# powersupply1.net
KiCad netlist of a schematic drawn in Altium Designer
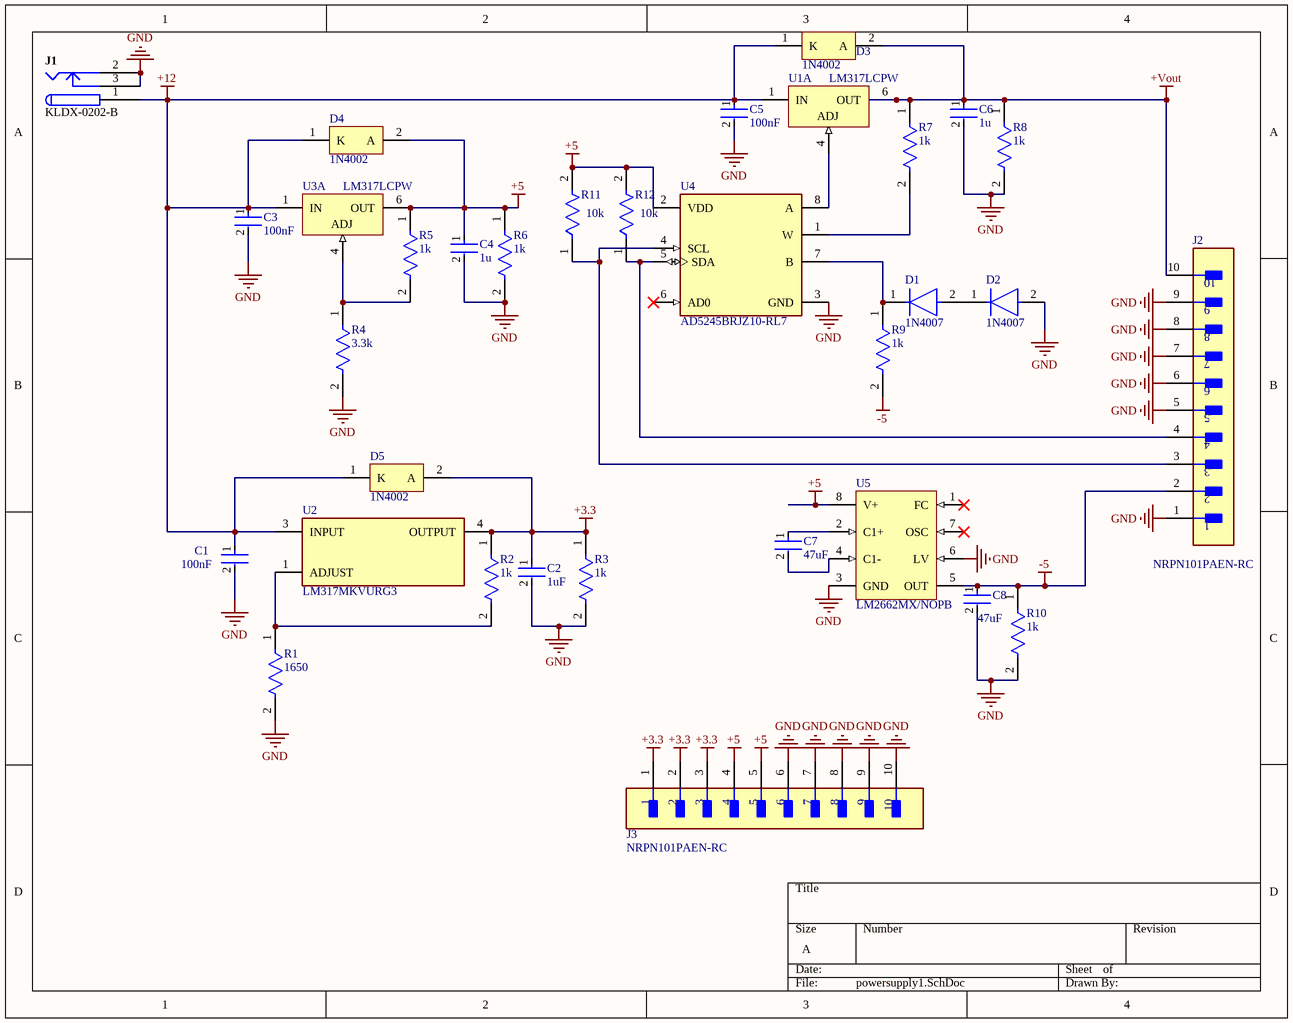
[diagram p0: powersupply1.SchDoc]

(export (version "E")
  (design (tool "Eeschema 10.0.6"))
  (components
    (comp (ref "C1")
      (value "100nF")
      (footprint "FP-CC0805-0_85-MFG")
      (description "CAP CER 0.1UF 25V X7R 0805")
      (fields (field (name "MANUFACTURER") "Yageo") (field (name "TOLERANCE") "0.2"))
      (libsource (lib "Altium Content Vault") (part "11868f565c42a9108669ba33697ecf6"))
    )
    (comp (ref "C2")
      (value "1uF")
      (footprint "FP-CC0805-0_85-MFG")
      (description "CAP CER 1UF 6.3V X5R 0805")
      (fields (field (name "MANUFACTURER") "Yageo") (field (name "TOLERANCE") "0.1"))
      (libsource (lib "Altium Content Vault") (part "11868f565c42a9108669ba33697ecf6"))
    )
    (comp (ref "C3")
      (value "100nF")
      (footprint "FP-CC0805-0_85-MFG")
      (description "CAP CER 0.1UF 25V X7R 0805")
      (fields (field (name "MANUFACTURER") "Yageo") (field (name "TOLERANCE") "0.2"))
      (libsource (lib "Altium Content Vault") (part "11868f565c42a9108669ba33697ecf6"))
    )
    (comp (ref "C4")
      (value "1u")
      (footprint "FP-CC0805-0_85-MFG")
      (description "CAP CER 1UF 6.3V X5R 0805")
      (fields (field (name "MANUFACTURER") "Yageo") (field (name "TOLERANCE") "0.1"))
      (libsource (lib "Altium Content Vault") (part "11868f565c42a9108669ba33697ecf6"))
    )
    (comp (ref "C5")
      (value "100nF")
      (footprint "FP-CC0805-0_85-MFG")
      (description "CAP CER 0.1UF 25V X7R 0805")
      (fields (field (name "MANUFACTURER") "Yageo") (field (name "TOLERANCE") "0.2"))
      (libsource (lib "Altium Content Vault") (part "11868f565c42a9108669ba33697ecf6"))
    )
    (comp (ref "C6")
      (value "1u")
      (footprint "FP-CC0805-0_85-MFG")
      (description "CAP CER 1UF 6.3V X5R 0805")
      (fields (field (name "MANUFACTURER") "Yageo") (field (name "TOLERANCE") "0.1"))
      (libsource (lib "Altium Content Vault") (part "11868f565c42a9108669ba33697ecf6"))
    )
    (comp (ref "C7")
      (value "47uF")
      (footprint "FP-GRM21B-0_2-e0_2_0_7-IPC_A")
      (description "Chip Multilayer Ceramic Capacitors for General Purpose, 0805, 47uF, X5R, 15%, 20%, 10V")
      (fields (field (name "TOLERANCE") "20%") (field (name "VOLTAGE") "10V"))
      (libsource (lib "Altium Content Vault") (part "b4654b650e69147ec39a6b967a45e02"))
    )
    (comp (ref "C8")
      (value "47uF")
      (footprint "FP-GRM21B-0_2-e0_2_0_7-IPC_A")
      (description "Chip Multilayer Ceramic Capacitors for General Purpose, 0805, 47uF, X5R, 15%, 20%, 10V")
      (fields (field (name "TOLERANCE") "20%") (field (name "VOLTAGE") "10V"))
      (libsource (lib "Altium Content Vault") (part "b4654b650e69147ec39a6b967a45e02"))
    )
    (comp (ref "D1")
      (value "1N4007")
      (footprint "FP-1N4007-MFG")
      (description "Rectifier diode 1000 V 1 A DO-41, ,")
      (fields
        (field (name "MANUFACTURER") "Diotec")
        (field (name "OCTOPART") "https://octopart.com/1n4007-diotec-4040411")
      )
      (libsource (lib "Altium Content Vault") (part "d7152d700b627762746794eb795d46e"))
    )
    (comp (ref "D2")
      (value "1N4007")
      (footprint "FP-1N4007-MFG")
      (description "Rectifier diode 1000 V 1 A DO-41, ,")
      (fields
        (field (name "MANUFACTURER") "Diotec")
        (field (name "OCTOPART") "https://octopart.com/1n4007-diotec-4040411")
      )
      (libsource (lib "Altium Content Vault") (part "d7152d700b627762746794eb795d46e"))
    )
    (comp (ref "D3")
      (value "1N4002")
      (footprint "ONSC-AXIAL_LEAD-2-59-10_P")
      (description "Standard Recovery Rectifier, 2-Pin Axial_Lead, Pb-Free, Bulk Bag")
      (fields (field (name "MANUFACTURER") "On Semiconductor"))
      (libsource (lib "Altium Content Vault") (part "ONSC-D-K1A2-2_A"))
    )
    (comp (ref "D4")
      (value "1N4002")
      (footprint "ONSC-AXIAL_LEAD-2-59-10_P")
      (description "Standard Recovery Rectifier, 2-Pin Axial_Lead, Pb-Free, Bulk Bag")
      (fields (field (name "MANUFACTURER") "On Semiconductor"))
      (libsource (lib "Altium Content Vault") (part "ONSC-D-K1A2-2_A"))
    )
    (comp (ref "D5")
      (value "1N4002")
      (footprint "ONSC-AXIAL_LEAD-2-59-10_P")
      (description "Standard Recovery Rectifier, 2-Pin Axial_Lead, Pb-Free, Bulk Bag")
      (fields (field (name "MANUFACTURER") "On Semiconductor"))
      (libsource (lib "Altium Content Vault") (part "ONSC-D-K1A2-2_A"))
    )
    (comp (ref "J1")
      (value "KLDX-0202-B")
      (footprint "KYCN-KLDX-0202-B_V")
      (description "3 Conductor Power Jack, 2 break 2 aux contacts")
      (libsource (lib "Altium Content Vault") (part "KYCN-KLDX-0202-B-3"))
    )
    (comp (ref "J2")
      (value "NRPN101PAEN-RC")
      (footprint "FP-NRPN101PAEN-RC-MFG")
      (description "CONN HEADER VERT 10POS 2MM")
      (fields
        (field (name "OCTOPART") "https://octopart.com/nrpn101paen-rc-sullins-18674398")
        (field (name "MANUFACTURER") "Sullins")
      )
      (libsource (lib "Altium Content Vault") (part "aee40dc8b284c03a16094555aa210be"))
    )
    (comp (ref "J3")
      (value "NRPN101PAEN-RC")
      (footprint "FP-NRPN101PAEN-RC-MFG")
      (description "CONN HEADER VERT 10POS 2MM")
      (fields
        (field (name "OCTOPART") "https://octopart.com/nrpn101paen-rc-sullins-18674398")
        (field (name "MANUFACTURER") "Sullins")
      )
      (libsource (lib "") (part "aee40dc8b284c03a16094555aa210be_1"))
    )
    (comp (ref "R1")
      (value "1650")
      (footprint "FP-RT0805-MFG")
      (description "RES SMD 1.65K OHM 1% 1/8W 0805")
      (fields
        (field (name "TOLERANCE") "0.0001")
        (field (name "OCTOPART") "https://octopart.com/rt0805fre071k65l-yageo-1226722")
      )
      (libsource (lib "Altium Content Vault") (part "1029c3af85768c4190bb7ad29bc67b5"))
    )
    (comp (ref "R2")
      (value "1k")
      (footprint "FP-RMCF0805-MFG")
      (description "1kΩ ±1% 0.125W 0805 Thick Film Chip Resistor AEC-Q200 compliant")
      (fields (field (name "TOLERANCE") "1%"))
      (libsource (lib "Altium Content Vault") (part "1029c3af85768c4190bb7ad29bc67b5"))
    )
    (comp (ref "R3")
      (value "1k")
      (footprint "FP-RMCF0805-MFG")
      (description "1kΩ ±1% 0.125W 0805 Thick Film Chip Resistor AEC-Q200 compliant")
      (fields (field (name "TOLERANCE") "1%"))
      (libsource (lib "Altium Content Vault") (part "1029c3af85768c4190bb7ad29bc67b5"))
    )
    (comp (ref "R4")
      (value "3.3k")
      (footprint "FP-CRGCQ0805-IPC_C")
      (description "CRGCQ0805 3.3KΩ 0.125W ±100ppm/°C 5% 150V")
      (fields (field (name "MANUFACTURER") "TE Connectivity") (field (name "TOLERANCE") "0.05"))
      (libsource (lib "Altium Content Vault") (part "1029c3af85768c4190bb7ad29bc67b5"))
    )
    (comp (ref "R5")
      (value "1k")
      (footprint "FP-RMCF0805-MFG")
      (description "1kΩ ±1% 0.125W 0805 Thick Film Chip Resistor AEC-Q200 compliant")
      (fields (field (name "TOLERANCE") "1%"))
      (libsource (lib "Altium Content Vault") (part "1029c3af85768c4190bb7ad29bc67b5"))
    )
    (comp (ref "R6")
      (value "1k")
      (footprint "FP-RMCF0805-MFG")
      (description "1kΩ ±1% 0.125W 0805 Thick Film Chip Resistor AEC-Q200 compliant")
      (fields (field (name "TOLERANCE") "1%"))
      (libsource (lib "Altium Content Vault") (part "1029c3af85768c4190bb7ad29bc67b5"))
    )
    (comp (ref "R7")
      (value "1k")
      (footprint "FP-RMCF0805-MFG")
      (description "1kΩ ±1% 0.125W 0805 Thick Film Chip Resistor AEC-Q200 compliant")
      (fields (field (name "TOLERANCE") "1%"))
      (libsource (lib "Altium Content Vault") (part "1029c3af85768c4190bb7ad29bc67b5"))
    )
    (comp (ref "R8")
      (value "1k")
      (footprint "FP-RMCF0805-MFG")
      (description "1kΩ ±1% 0.125W 0805 Thick Film Chip Resistor AEC-Q200 compliant")
      (fields (field (name "TOLERANCE") "1%"))
      (libsource (lib "Altium Content Vault") (part "1029c3af85768c4190bb7ad29bc67b5"))
    )
    (comp (ref "R9")
      (value "1k")
      (footprint "FP-RMCF0805-MFG")
      (description "1kΩ ±1% 0.125W 0805 Thick Film Chip Resistor AEC-Q200 compliant")
      (fields (field (name "TOLERANCE") "1%"))
      (libsource (lib "Altium Content Vault") (part "1029c3af85768c4190bb7ad29bc67b5"))
    )
    (comp (ref "R10")
      (value "1k")
      (footprint "FP-RMCF0805-MFG")
      (description "1kΩ ±1% 0.125W 0805 Thick Film Chip Resistor AEC-Q200 compliant")
      (fields (field (name "TOLERANCE") "1%"))
      (libsource (lib "Altium Content Vault") (part "1029c3af85768c4190bb7ad29bc67b5"))
    )
    (comp (ref "R11")
      (value "10k")
      (footprint "FP-RT0805-MFG")
      (description "RES SMD 10K OHM 1% 1/8W 0805")
      (fields
        (field (name "OCTOPART") "https://octopart.com/rt0805frd0710kl-yageo-71399701")
        (field (name "TOLERANCE") "0.0001")
      )
      (libsource (lib "Altium Content Vault") (part "1029c3af85768c4190bb7ad29bc67b5"))
    )
    (comp (ref "R12")
      (value "10k")
      (footprint "FP-RT0805-MFG")
      (description "RES SMD 10K OHM 1% 1/8W 0805")
      (fields
        (field (name "OCTOPART") "https://octopart.com/rt0805frd0710kl-yageo-71399701")
        (field (name "TOLERANCE") "0.0001")
      )
      (libsource (lib "Altium Content Vault") (part "1029c3af85768c4190bb7ad29bc67b5"))
    )
    (comp (ref "U1")
      (value "LM317LCPW")
      (footprint "PW0008A_L")
      (fields (field (name "MANUFACTURER") "Texas Instruments"))
      (libsource (lib "Altium Content Vault") (part "TI-LM317LPW8"))
    )
    (comp (ref "U2")
      (value "LM317MKVURG3")
      (footprint "FP-KVU0003A-MFG")
      (description "IC REG LIN POS ADJ 500MA TO252-3")
      (libsource (lib "Altium Content Vault") (part "56627df6dd48f1ca4f90921aa44f780"))
    )
    (comp (ref "U3")
      (value "LM317LCPW")
      (footprint "PW0008A_L")
      (fields (field (name "MANUFACTURER") "Texas Instruments"))
      (libsource (lib "Altium Content Vault") (part "TI-LM317LPW8"))
    )
    (comp (ref "U4")
      (value "AD5245BRJZ10-RL7")
      (footprint "FP-RJ-8-IPC_B")
      (description "IC DGT POT 10KOHM 256TAP SOT23-8")
      (fields (field (name "TOLERANCE") "30%"))
      (libsource (lib "Altium Content Vault") (part "777f9caa62b19d2ac513b26aa3e00a4"))
    )
    (comp (ref "U5")
      (value "LM2662MX/NOPB")
      (footprint "D0008A_M")
      (description "Switched Capacitor Voltage Converter, 8-pin Narrow SOIC, Pb-Free")
      (fields (field (name "MANUFACTURER") "Texas Instruments"))
      (libsource (lib "Altium Content Vault") (part "PM-CHP-LM2660M-8"))
    )
  )
  (nets
    (net (code "1") (name "+3.3") (class "Default")
      (node (ref "C2") (pin "1") (pinfunction "1_1") (pintype "passive"))
      (node (ref "D5") (pin "2") (pinfunction "A_2") (pintype "passive"))
      (node (ref "J3") (pin "1") (pinfunction "1_1") (pintype "passive"))
      (node (ref "J3") (pin "2") (pinfunction "2_2") (pintype "passive"))
      (node (ref "J3") (pin "3") (pinfunction "3_3") (pintype "passive"))
      (node (ref "R2") (pin "1") (pinfunction "1_1") (pintype "passive"))
      (node (ref "R3") (pin "1") (pinfunction "1_1") (pintype "passive"))
      (node (ref "U2") (pin "4") (pinfunction "OUTPUT_4") (pintype "power_in"))
    )
    (net (code "2") (name "+5") (class "Default")
      (node (ref "C4") (pin "1") (pinfunction "1_1") (pintype "passive"))
      (node (ref "D4") (pin "2") (pinfunction "A_2") (pintype "passive"))
      (node (ref "J3") (pin "4") (pinfunction "4_4") (pintype "passive"))
      (node (ref "J3") (pin "5") (pinfunction "5_5") (pintype "passive"))
      (node (ref "R11") (pin "2") (pinfunction "2_2") (pintype "passive"))
      (node (ref "R12") (pin "2") (pinfunction "2_2") (pintype "passive"))
      (node (ref "R5") (pin "1") (pinfunction "1_1") (pintype "passive"))
      (node (ref "R6") (pin "1") (pinfunction "1_1") (pintype "passive"))
      (node (ref "U3") (pin "6") (pinfunction "OUT_6") (pintype "power_in"))
      (node (ref "U4") (pin "2") (pinfunction "VDD_2") (pintype "power_in"))
      (node (ref "U5") (pin "8") (pinfunction "V+_8") (pintype "power_in"))
    )
    (net (code "3") (name "+12") (class "Default")
      (node (ref "C1") (pin "1") (pinfunction "1_1") (pintype "passive"))
      (node (ref "C3") (pin "1") (pinfunction "1_1") (pintype "passive"))
      (node (ref "C5") (pin "1") (pinfunction "1_1") (pintype "passive"))
      (node (ref "D3") (pin "1") (pinfunction "K_1") (pintype "passive"))
      (node (ref "D4") (pin "1") (pinfunction "K_1") (pintype "passive"))
      (node (ref "D5") (pin "1") (pinfunction "K_1") (pintype "passive"))
      (node (ref "J1") (pin "1") (pintype "power_in"))
      (node (ref "U1") (pin "1") (pinfunction "IN_1") (pintype "power_in"))
      (node (ref "U2") (pin "3") (pinfunction "INPUT_3") (pintype "power_in"))
      (node (ref "U3") (pin "1") (pinfunction "IN_1") (pintype "power_in"))
    )
    (net (code "4") (name "+Vout") (class "Default")
      (node (ref "C6") (pin "1") (pinfunction "1_1") (pintype "passive"))
      (node (ref "D3") (pin "2") (pinfunction "A_2") (pintype "passive"))
      (node (ref "J2") (pin "10") (pinfunction "10_10") (pintype "passive"))
      (node (ref "R7") (pin "1") (pinfunction "1_1") (pintype "passive"))
      (node (ref "R8") (pin "1") (pinfunction "1_1") (pintype "passive"))
      (node (ref "U1") (pin "6") (pinfunction "OUT_6") (pintype "power_in"))
    )
    (net (code "5") (name "-5") (class "Default")
      (node (ref "C8") (pin "1") (pinfunction "1_1") (pintype "passive"))
      (node (ref "J2") (pin "2") (pinfunction "2_2") (pintype "passive"))
      (node (ref "R10") (pin "1") (pinfunction "1_1") (pintype "passive"))
      (node (ref "R9") (pin "2") (pinfunction "2_2") (pintype "passive"))
      (node (ref "U5") (pin "5") (pinfunction "OUT_5") (pintype "power_in"))
    )
    (net (code "6") (name "GND") (class "Default")
      (node (ref "C1") (pin "2") (pinfunction "2_2") (pintype "passive"))
      (node (ref "C2") (pin "2") (pinfunction "2_2") (pintype "passive"))
      (node (ref "C3") (pin "2") (pinfunction "2_2") (pintype "passive"))
      (node (ref "C4") (pin "2") (pinfunction "2_2") (pintype "passive"))
      (node (ref "C5") (pin "2") (pinfunction "2_2") (pintype "passive"))
      (node (ref "C6") (pin "2") (pinfunction "2_2") (pintype "passive"))
      (node (ref "C8") (pin "2") (pinfunction "2_2") (pintype "passive"))
      (node (ref "D2") (pin "2") (pinfunction "A_2") (pintype "passive"))
      (node (ref "J1") (pin "2") (pintype "power_in"))
      (node (ref "J1") (pin "3") (pintype "power_in"))
      (node (ref "J2") (pin "1") (pinfunction "1_1") (pintype "passive"))
      (node (ref "J2") (pin "5") (pinfunction "5_5") (pintype "passive"))
      (node (ref "J2") (pin "6") (pinfunction "6_6") (pintype "passive"))
      (node (ref "J2") (pin "7") (pinfunction "7_7") (pintype "passive"))
      (node (ref "J2") (pin "8") (pinfunction "8_8") (pintype "passive"))
      (node (ref "J2") (pin "9") (pinfunction "9_9") (pintype "passive"))
      (node (ref "J3") (pin "10") (pinfunction "10_10") (pintype "passive"))
      (node (ref "J3") (pin "6") (pinfunction "6_6") (pintype "passive"))
      (node (ref "J3") (pin "7") (pinfunction "7_7") (pintype "passive"))
      (node (ref "J3") (pin "8") (pinfunction "8_8") (pintype "passive"))
      (node (ref "J3") (pin "9") (pinfunction "9_9") (pintype "passive"))
      (node (ref "R1") (pin "2") (pinfunction "2_2") (pintype "passive"))
      (node (ref "R10") (pin "2") (pinfunction "2_2") (pintype "passive"))
      (node (ref "R3") (pin "2") (pinfunction "2_2") (pintype "passive"))
      (node (ref "R4") (pin "2") (pinfunction "2_2") (pintype "passive"))
      (node (ref "R6") (pin "2") (pinfunction "2_2") (pintype "passive"))
      (node (ref "R8") (pin "2") (pinfunction "2_2") (pintype "passive"))
      (node (ref "U4") (pin "3") (pinfunction "GND_3") (pintype "power_in"))
      (node (ref "U5") (pin "3") (pinfunction "GND_3") (pintype "power_in"))
      (node (ref "U5") (pin "6") (pinfunction "LV_6") (pintype "input"))
    )
    (net (code "7") (name "Net-(D1-A)") (class "Default")
      (node (ref "D1") (pin "2") (pinfunction "A_2") (pintype "passive"))
      (node (ref "D2") (pin "1") (pinfunction "C_1") (pintype "passive"))
    )
    (net (code "8") (name "Net-(D1-C)") (class "Default")
      (node (ref "D1") (pin "1") (pinfunction "C_1") (pintype "passive"))
      (node (ref "R9") (pin "1") (pinfunction "1_1") (pintype "passive"))
      (node (ref "U4") (pin "7") (pinfunction "B_7") (pintype "passive"))
    )
    (net (code "9") (name "Net-(U1A-ADJ)") (class "Default")
      (node (ref "U1") (pin "4") (pinfunction "ADJ_4") (pintype "input"))
      (node (ref "U4") (pin "8") (pinfunction "A_8") (pintype "passive"))
    )
    (net (code "10") (name "Net-(U2-ADJUST)") (class "Default")
      (node (ref "R1") (pin "1") (pinfunction "1_1") (pintype "passive"))
      (node (ref "R2") (pin "2") (pinfunction "2_2") (pintype "passive"))
      (node (ref "U2") (pin "1") (pinfunction "ADJUST_1") (pintype "passive"))
    )
    (net (code "11") (name "Net-(U3A-ADJ)") (class "Default")
      (node (ref "R4") (pin "1") (pinfunction "1_1") (pintype "passive"))
      (node (ref "R5") (pin "2") (pinfunction "2_2") (pintype "passive"))
      (node (ref "U3") (pin "4") (pinfunction "ADJ_4") (pintype "input"))
    )
    (net (code "12") (name "Net-(U4-SCL)") (class "Default")
      (node (ref "J2") (pin "3") (pinfunction "3_3") (pintype "passive"))
      (node (ref "R11") (pin "1") (pinfunction "1_1") (pintype "passive"))
      (node (ref "U4") (pin "4") (pinfunction "SCL_4") (pintype "input"))
    )
    (net (code "13") (name "Net-(U4-SDA)") (class "Default")
      (node (ref "J2") (pin "4") (pinfunction "4_4") (pintype "passive"))
      (node (ref "R12") (pin "1") (pinfunction "1_1") (pintype "passive"))
      (node (ref "U4") (pin "5") (pinfunction "SDA_5") (pintype "bidirectional"))
    )
    (net (code "14") (name "Net-(U4-W)") (class "Default")
      (node (ref "R7") (pin "2") (pinfunction "2_2") (pintype "passive"))
      (node (ref "U4") (pin "1") (pinfunction "W_1") (pintype "passive"))
    )
    (net (code "15") (name "Net-(U5-C1+)") (class "Default")
      (node (ref "C7") (pin "1") (pinfunction "1_1") (pintype "passive"))
      (node (ref "U5") (pin "2") (pinfunction "C1+_2") (pintype "input"))
    )
    (net (code "16") (name "Net-(U5-C1-)") (class "Default")
      (node (ref "C7") (pin "2") (pinfunction "2_2") (pintype "passive"))
      (node (ref "U5") (pin "4") (pinfunction "C1-_4") (pintype "input"))
    )
    (net (code "17") (name "unconnected-(U4-AD0-Pad6)") (class "Default")
      (node (ref "U4") (pin "6") (pinfunction "AD0_6") (pintype "input+no_connect"))
    )
    (net (code "18") (name "unconnected-(U5-FC-Pad1)") (class "Default")
      (node (ref "U5") (pin "1") (pinfunction "FC_1") (pintype "input+no_connect"))
    )
    (net (code "19") (name "unconnected-(U5-OSC-Pad7)") (class "Default")
      (node (ref "U5") (pin "7") (pinfunction "OSC_7") (pintype "input+no_connect"))
    )
  )
)
